# FDTI_converter_out.net
KiCad netlist of a schematic drawn in Altium Designer
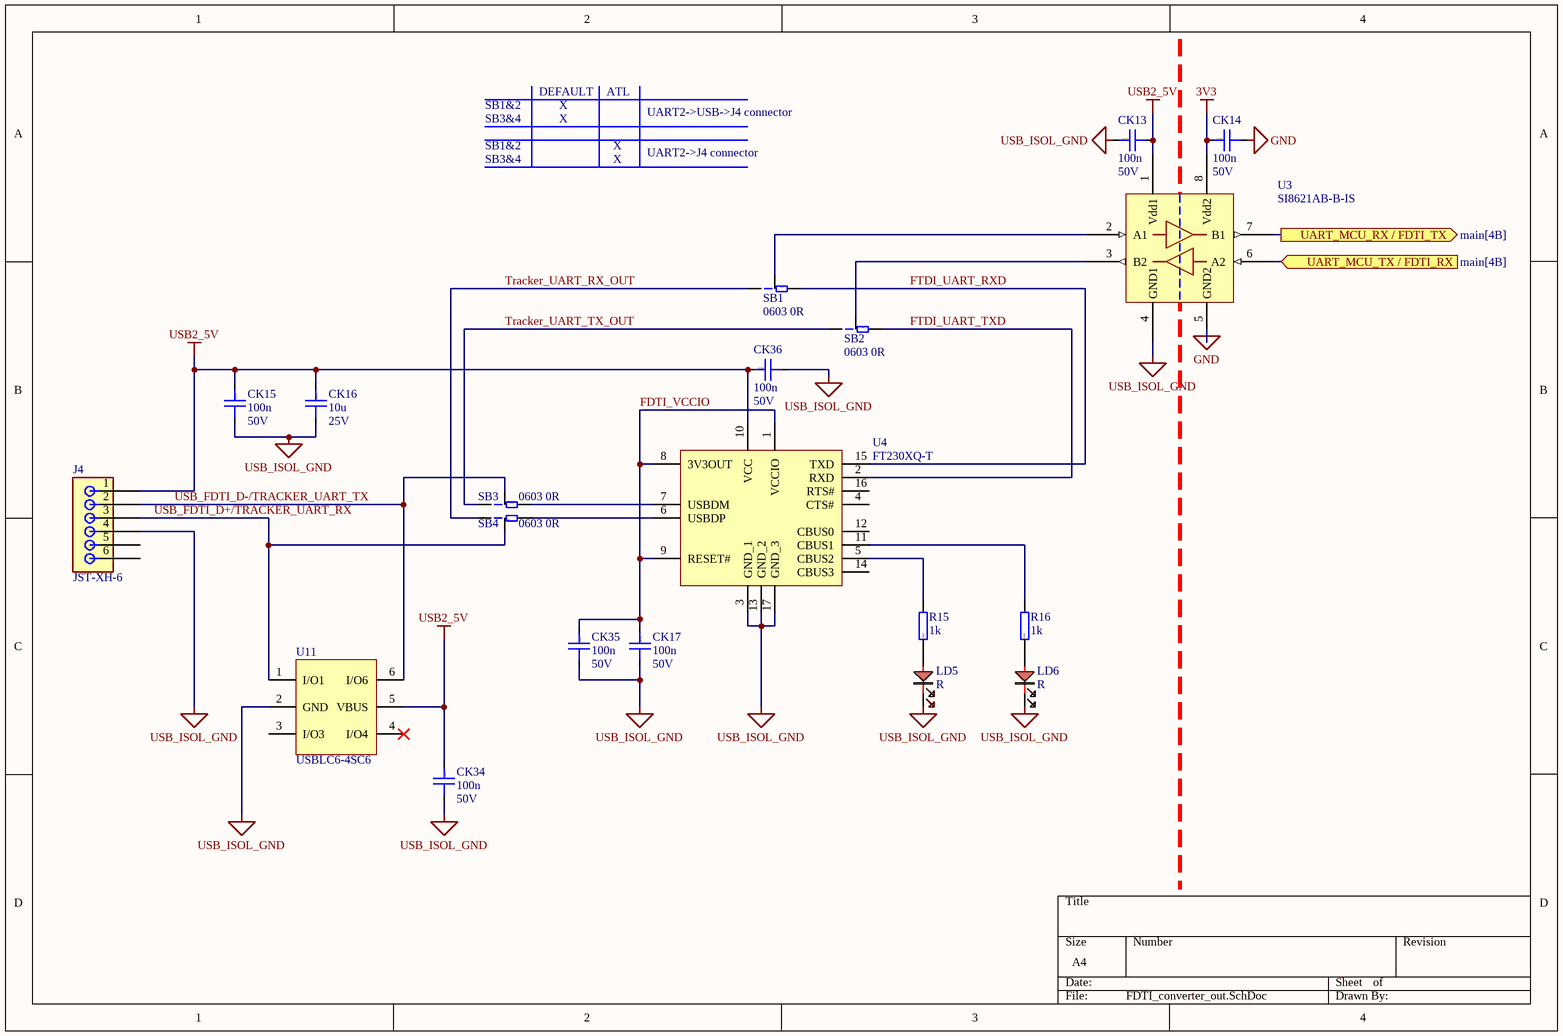
[diagram p0: FDTI_converter_out.SchDoc]

(export (version "E")
  (design (tool "Eeschema 10.0.6"))
  (components
    (comp (ref "CK13")
      (value "100n")
      (footprint "CAP0603")
      (description "50V 100nF X7R ±10% 0603 Multilayer Ceramic Capacitors MLCC - SMD/SMT ROHS")
      (fields (field (name "JLCPCB PART") "C14663") (field (name "VOLTAGE RATING") "50V"))
      (libsource (lib "Kubikova ultra knihovna") (part "Cap 100n 50V 0603"))
    )
    (comp (ref "CK14")
      (value "100n")
      (footprint "CAP0603")
      (description "50V 100nF X7R ±10% 0603 Multilayer Ceramic Capacitors MLCC - SMD/SMT ROHS")
      (fields (field (name "JLCPCB PART") "C14663") (field (name "VOLTAGE RATING") "50V"))
      (libsource (lib "Kubikova ultra knihovna") (part "Cap 100n 50V 0603"))
    )
    (comp (ref "CK15")
      (value "100n")
      (footprint "CAP0603")
      (description "50V 100nF X7R ±10% 0603 Multilayer Ceramic Capacitors MLCC - SMD/SMT ROHS")
      (fields (field (name "JLCPCB PART") "C14663") (field (name "VOLTAGE RATING") "50V"))
      (libsource (lib "Kubikova ultra knihovna") (part "Cap 100n 50V 0603"))
    )
    (comp (ref "CK16")
      (value "10u")
      (footprint "CAP0805")
      (description "25V 10uF X5R ±10% 0805 Multilayer Ceramic Capacitors MLCC - SMD/SMT ROHS")
      (fields (field (name "JLCPCB PART") "C15850") (field (name "VOLTAGE RATING") "25V"))
      (libsource (lib "Kubikova ultra knihovna") (part "Cap 10u 0805"))
    )
    (comp (ref "CK17")
      (value "100n")
      (footprint "CAP0603")
      (description "50V 100nF X7R ±10% 0603 Multilayer Ceramic Capacitors MLCC - SMD/SMT ROHS")
      (fields (field (name "JLCPCB PART") "C14663") (field (name "VOLTAGE RATING") "50V"))
      (libsource (lib "Kubikova ultra knihovna") (part "Cap 100n 50V 0603"))
    )
    (comp (ref "CK34")
      (value "100n")
      (footprint "CAP0603")
      (description "50V 100nF X7R ±10% 0603 Multilayer Ceramic Capacitors MLCC - SMD/SMT ROHS")
      (fields (field (name "JLCPCB PART") "C14663") (field (name "VOLTAGE RATING") "50V"))
      (libsource (lib "Kubikova ultra knihovna") (part "Cap 100n 0603"))
    )
    (comp (ref "CK35")
      (value "100n")
      (footprint "CAP0603")
      (description "50V 100nF X7R ±10% 0603 Multilayer Ceramic Capacitors MLCC - SMD/SMT ROHS")
      (fields (field (name "JLCPCB PART") "C14663") (field (name "VOLTAGE RATING") "50V"))
      (libsource (lib "Kubikova ultra knihovna") (part "Cap 100n 50V 0603"))
    )
    (comp (ref "CK36")
      (value "100n")
      (footprint "CAP0603")
      (description "50V 100nF X7R ±10% 0603 Multilayer Ceramic Capacitors MLCC - SMD/SMT ROHS")
      (fields (field (name "JLCPCB PART") "C14663") (field (name "VOLTAGE RATING") "50V"))
      (libsource (lib "Kubikova ultra knihovna") (part "Cap 100n 50V 0603"))
    )
    (comp (ref "J4")
      (value "JST-XH-6")
      (footprint "JST-XH-6")
      (fields (field (name "JLCPCB PART") "C157919") (field (name "TME PART") "S6B-XH-A"))
      (libsource (lib "Kubikova ultra knihovna") (part "JST-HX-6"))
    )
    (comp (ref "LD5")
      (value "R")
      (footprint "0603_LED_R")
      (description "-40℃~+85℃ Red 0603 LED Indication - Discrete ROHS")
      (fields (field (name "JLCPCB PART") "C2286"))
      (libsource (lib "Kubikova ultra knihovna") (part "LED R 0603"))
    )
    (comp (ref "LD6")
      (value "R")
      (footprint "0603_LED_R")
      (description "-40℃~+85℃ Red 0603 LED Indication - Discrete ROHS")
      (fields (field (name "JLCPCB PART") "C2286"))
      (libsource (lib "Kubikova ultra knihovna") (part "LED R 0603"))
    )
    (comp (ref "R15")
      (value "1k")
      (footprint "RESC2012X06N(SMR0805)")
      (description "125mW Thick Film Resistors 150V ±100ppm/℃ ±1% 1kΩ 0805 Chip Resistor - Surface Mount ROHS")
      (fields (field (name "JLCPCB PART") "C17513") (field (name "AUTHOR") "JP/27.03.2014"))
      (libsource (lib "Kubikova ultra knihovna") (part "Res 1k 0805"))
    )
    (comp (ref "R16")
      (value "1k")
      (footprint "RESC2012X06N(SMR0805)")
      (description "125mW Thick Film Resistors 150V ±100ppm/℃ ±1% 1kΩ 0805 Chip Resistor - Surface Mount ROHS")
      (fields (field (name "JLCPCB PART") "C17513") (field (name "AUTHOR") "JP/27.03.2014"))
      (libsource (lib "Kubikova ultra knihovna") (part "Res 1k 0805"))
    )
    (comp (ref "SB1")
      (value "0603 0R")
      (footprint "Solder T bridge 0603")
      (fields (field (name "JLCPCB PART") "C21189"))
      (libsource (lib "Kubikova ultra knihovna") (part "0R T-junction"))
    )
    (comp (ref "SB2")
      (value "0603 0R")
      (footprint "Solder T bridge 0603")
      (fields (field (name "JLCPCB PART") "C21189"))
      (libsource (lib "Kubikova ultra knihovna") (part "0R T-junction"))
    )
    (comp (ref "SB3")
      (value "0603 0R")
      (footprint "Solder T bridge 0603")
      (fields (field (name "JLCPCB PART") "C21189"))
      (libsource (lib "Kubikova ultra knihovna") (part "0R T-junction"))
    )
    (comp (ref "SB4")
      (value "0603 0R")
      (footprint "Solder T bridge 0603")
      (fields (field (name "JLCPCB PART") "C21189"))
      (libsource (lib "Kubikova ultra knihovna") (part "0R T-junction"))
    )
    (comp (ref "U3")
      (value "SI8621AB-B-IS")
      (footprint "SOIC8")
      (description "SOIC-8 Digital Isolators ROHS")
      (fields (field (name "JLCPCB PART") "C430265"))
      (libsource (lib "Kubikova ultra knihovna") (part "SI8621AB-B-IS"))
    )
    (comp (ref "U4")
      (value "FT230XQ-T")
      (footprint "Kubikova pcb knihovna:QFN65P400X400X80-17N")
      (description "Integrated Circuit")
      (fields (field (name "MOUSER PART NUMBER") "895-FT230XQ-T") (field (name "JLCPCB PART") "C3216402"))
      (libsource (lib "Kubikova ultra knihovna") (part "FT230XQ-T"))
    )
    (comp (ref "U11")
      (value "USBLC6-4SC6")
      (footprint "SOT23-6")
      (description "5A 17V 6V Unidirectional 5.25V SOT-23-6 ESD and Surge Protection (TVS/ESD) ROHS")
      (fields (field (name "JLCPCB PART") "C111212"))
      (libsource (lib "Kubikova ultra knihovna") (part "USBLC6-4SC6"))
    )
  )
  (nets
    (net (code "1") (name "/FDTI_VCCIO") (class "Default")
      (node (ref "CK17") (pin "1") (pinfunction "1_1") (pintype "passive"))
      (node (ref "CK35") (pin "1") (pinfunction "1_1") (pintype "passive"))
      (node (ref "U4") (pin "1") (pinfunction "VCCIO_1") (pintype "passive"))
      (node (ref "U4") (pin "8") (pinfunction "3V3OUT_8") (pintype "passive"))
      (node (ref "U4") (pin "9") (pinfunction "RESET#_9") (pintype "passive"))
    )
    (net (code "2") (name "/FTDI_UART_RXD") (class "Default")
      (node (ref "SB1") (pin "3") (pinfunction "3_3") (pintype "passive"))
      (node (ref "U4") (pin "15") (pinfunction "TXD_15") (pintype "passive"))
    )
    (net (code "3") (name "/FTDI_UART_TXD") (class "Default")
      (node (ref "SB2") (pin "3") (pinfunction "3_3") (pintype "passive"))
      (node (ref "U4") (pin "2") (pinfunction "RXD_2") (pintype "passive"))
    )
    (net (code "4") (name "/Tracker_UART_RX_OUT") (class "Default")
      (node (ref "SB1") (pin "1") (pinfunction "1_1") (pintype "passive"))
      (node (ref "SB4") (pin "1") (pinfunction "1_1") (pintype "passive"))
    )
    (net (code "5") (name "/Tracker_UART_TX_OUT") (class "Default")
      (node (ref "SB2") (pin "1") (pinfunction "1_1") (pintype "passive"))
      (node (ref "SB3") (pin "1") (pinfunction "1_1") (pintype "passive"))
    )
    (net (code "6") (name "/UART_MCU_RX {slash} FDTI_TX") (class "Default")
      (node (ref "U3") (pin "7") (pinfunction "B1_7") (pintype "output"))
    )
    (net (code "7") (name "/UART_MCU_TX {slash} FDTI_RX") (class "Default")
      (node (ref "U3") (pin "6") (pinfunction "A2_6") (pintype "input"))
    )
    (net (code "8") (name "/USB_FDTI_D+{slash}TRACKER_UART_RX") (class "Default")
      (node (ref "J4") (pin "3") (pinfunction "3_3") (pintype "passive"))
      (node (ref "SB4") (pin "2") (pinfunction "2_2") (pintype "passive"))
      (node (ref "U11") (pin "1") (pinfunction "I/O1_1") (pintype "passive"))
    )
    (net (code "9") (name "/USB_FDTI_D-{slash}TRACKER_UART_TX") (class "Default")
      (node (ref "J4") (pin "2") (pinfunction "2_2") (pintype "passive"))
      (node (ref "SB3") (pin "2") (pinfunction "2_2") (pintype "passive"))
      (node (ref "U11") (pin "6") (pinfunction "I/O6_6") (pintype "passive"))
    )
    (net (code "10") (name "3V3") (class "Default")
      (node (ref "CK14") (pin "1") (pinfunction "1_1") (pintype "passive"))
      (node (ref "U3") (pin "8") (pinfunction "Vdd2_8") (pintype "power_in"))
    )
    (net (code "11") (name "GND") (class "Default")
      (node (ref "CK14") (pin "2") (pinfunction "2_2") (pintype "passive"))
      (node (ref "U3") (pin "5") (pinfunction "GND2_5") (pintype "power_in"))
    )
    (net (code "12") (name "Net-(LD5-Pad1)") (class "Default")
      (node (ref "LD5") (pin "1") (pintype "passive"))
      (node (ref "R15") (pin "2") (pinfunction "2_2") (pintype "passive"))
    )
    (net (code "13") (name "Net-(LD6-Pad1)") (class "Default")
      (node (ref "LD6") (pin "1") (pintype "passive"))
      (node (ref "R16") (pin "2") (pinfunction "2_2") (pintype "passive"))
    )
    (net (code "14") (name "Net-(U3-A1)") (class "Default")
      (node (ref "SB1") (pin "2") (pinfunction "2_2") (pintype "passive"))
      (node (ref "U3") (pin "2") (pinfunction "A1_2") (pintype "input"))
    )
    (net (code "15") (name "Net-(U3-B2)") (class "Default")
      (node (ref "SB2") (pin "2") (pinfunction "2_2") (pintype "passive"))
      (node (ref "U3") (pin "3") (pinfunction "B2_3") (pintype "output"))
    )
    (net (code "16") (name "Net-(U4-CBUS1)") (class "Default")
      (node (ref "R16") (pin "1") (pinfunction "1_1") (pintype "passive"))
      (node (ref "U4") (pin "11") (pinfunction "CBUS1_11") (pintype "passive"))
    )
    (net (code "17") (name "Net-(U4-CBUS2)") (class "Default")
      (node (ref "R15") (pin "1") (pinfunction "1_1") (pintype "passive"))
      (node (ref "U4") (pin "5") (pinfunction "CBUS2_5") (pintype "passive"))
    )
    (net (code "18") (name "Net-(U4-USBDM)") (class "Default")
      (node (ref "SB3") (pin "3") (pinfunction "3_3") (pintype "passive"))
      (node (ref "U4") (pin "7") (pinfunction "USBDM_7") (pintype "passive"))
    )
    (net (code "19") (name "Net-(U4-USBDP)") (class "Default")
      (node (ref "SB4") (pin "3") (pinfunction "3_3") (pintype "passive"))
      (node (ref "U4") (pin "6") (pinfunction "USBDP_6") (pintype "passive"))
    )
    (net (code "20") (name "USB2_5V") (class "Default")
      (node (ref "CK13") (pin "2") (pinfunction "2_2") (pintype "passive"))
      (node (ref "CK15") (pin "1") (pinfunction "1_1") (pintype "passive"))
      (node (ref "CK16") (pin "1") (pinfunction "1_1") (pintype "passive"))
      (node (ref "CK34") (pin "1") (pinfunction "1_1") (pintype "passive"))
      (node (ref "CK36") (pin "1") (pinfunction "1_1") (pintype "passive"))
      (node (ref "J4") (pin "1") (pinfunction "1_1") (pintype "passive"))
      (node (ref "U11") (pin "5") (pinfunction "VBUS_5") (pintype "passive"))
      (node (ref "U3") (pin "1") (pinfunction "Vdd1_1") (pintype "power_in"))
      (node (ref "U4") (pin "10") (pinfunction "VCC_10") (pintype "passive"))
    )
    (net (code "21") (name "USB_ISOL_GND") (class "Default")
      (node (ref "CK13") (pin "1") (pinfunction "1_1") (pintype "passive"))
      (node (ref "CK15") (pin "2") (pinfunction "2_2") (pintype "passive"))
      (node (ref "CK16") (pin "2") (pinfunction "2_2") (pintype "passive"))
      (node (ref "CK17") (pin "2") (pinfunction "2_2") (pintype "passive"))
      (node (ref "CK34") (pin "2") (pinfunction "2_2") (pintype "passive"))
      (node (ref "CK35") (pin "2") (pinfunction "2_2") (pintype "passive"))
      (node (ref "CK36") (pin "2") (pinfunction "2_2") (pintype "passive"))
      (node (ref "J4") (pin "4") (pinfunction "4_4") (pintype "passive"))
      (node (ref "LD5") (pin "2") (pintype "passive"))
      (node (ref "LD6") (pin "2") (pintype "passive"))
      (node (ref "U11") (pin "2") (pinfunction "GND_2") (pintype "passive"))
      (node (ref "U3") (pin "4") (pinfunction "GND1_4") (pintype "power_in"))
      (node (ref "U4") (pin "13") (pinfunction "GND_2_13") (pintype "passive"))
      (node (ref "U4") (pin "17") (pinfunction "GND_3_17") (pintype "passive"))
      (node (ref "U4") (pin "3") (pinfunction "GND_1_3") (pintype "passive"))
    )
    (net (code "22") (name "unconnected-(J4-Pad5)") (class "Default")
      (node (ref "J4") (pin "5") (pinfunction "5_5") (pintype "passive"))
    )
    (net (code "23") (name "unconnected-(J4-Pad6)") (class "Default")
      (node (ref "J4") (pin "6") (pinfunction "6_6") (pintype "passive"))
    )
    (net (code "24") (name "unconnected-(U4-CBUS0-Pad12)") (class "Default")
      (node (ref "U4") (pin "12") (pinfunction "CBUS0_12") (pintype "passive"))
    )
    (net (code "25") (name "unconnected-(U4-CBUS3-Pad14)") (class "Default")
      (node (ref "U4") (pin "14") (pinfunction "CBUS3_14") (pintype "passive"))
    )
    (net (code "26") (name "unconnected-(U4-CTS#-Pad4)") (class "Default")
      (node (ref "U4") (pin "4") (pinfunction "CTS#_4") (pintype "passive"))
    )
    (net (code "27") (name "unconnected-(U4-RTS#-Pad16)") (class "Default")
      (node (ref "U4") (pin "16") (pinfunction "RTS#_16") (pintype "passive"))
    )
    (net (code "28") (name "unconnected-(U11-I{slash}O3-Pad3)") (class "Default")
      (node (ref "U11") (pin "3") (pinfunction "I/O3_3") (pintype "passive"))
    )
    (net (code "29") (name "unconnected-(U11-I{slash}O4-Pad4)") (class "Default")
      (node (ref "U11") (pin "4") (pinfunction "I/O4_4") (pintype "passive+no_connect"))
    )
  )
)
